# 03_HDMI_TX.net
KiCad netlist of a schematic drawn in Altium Designer
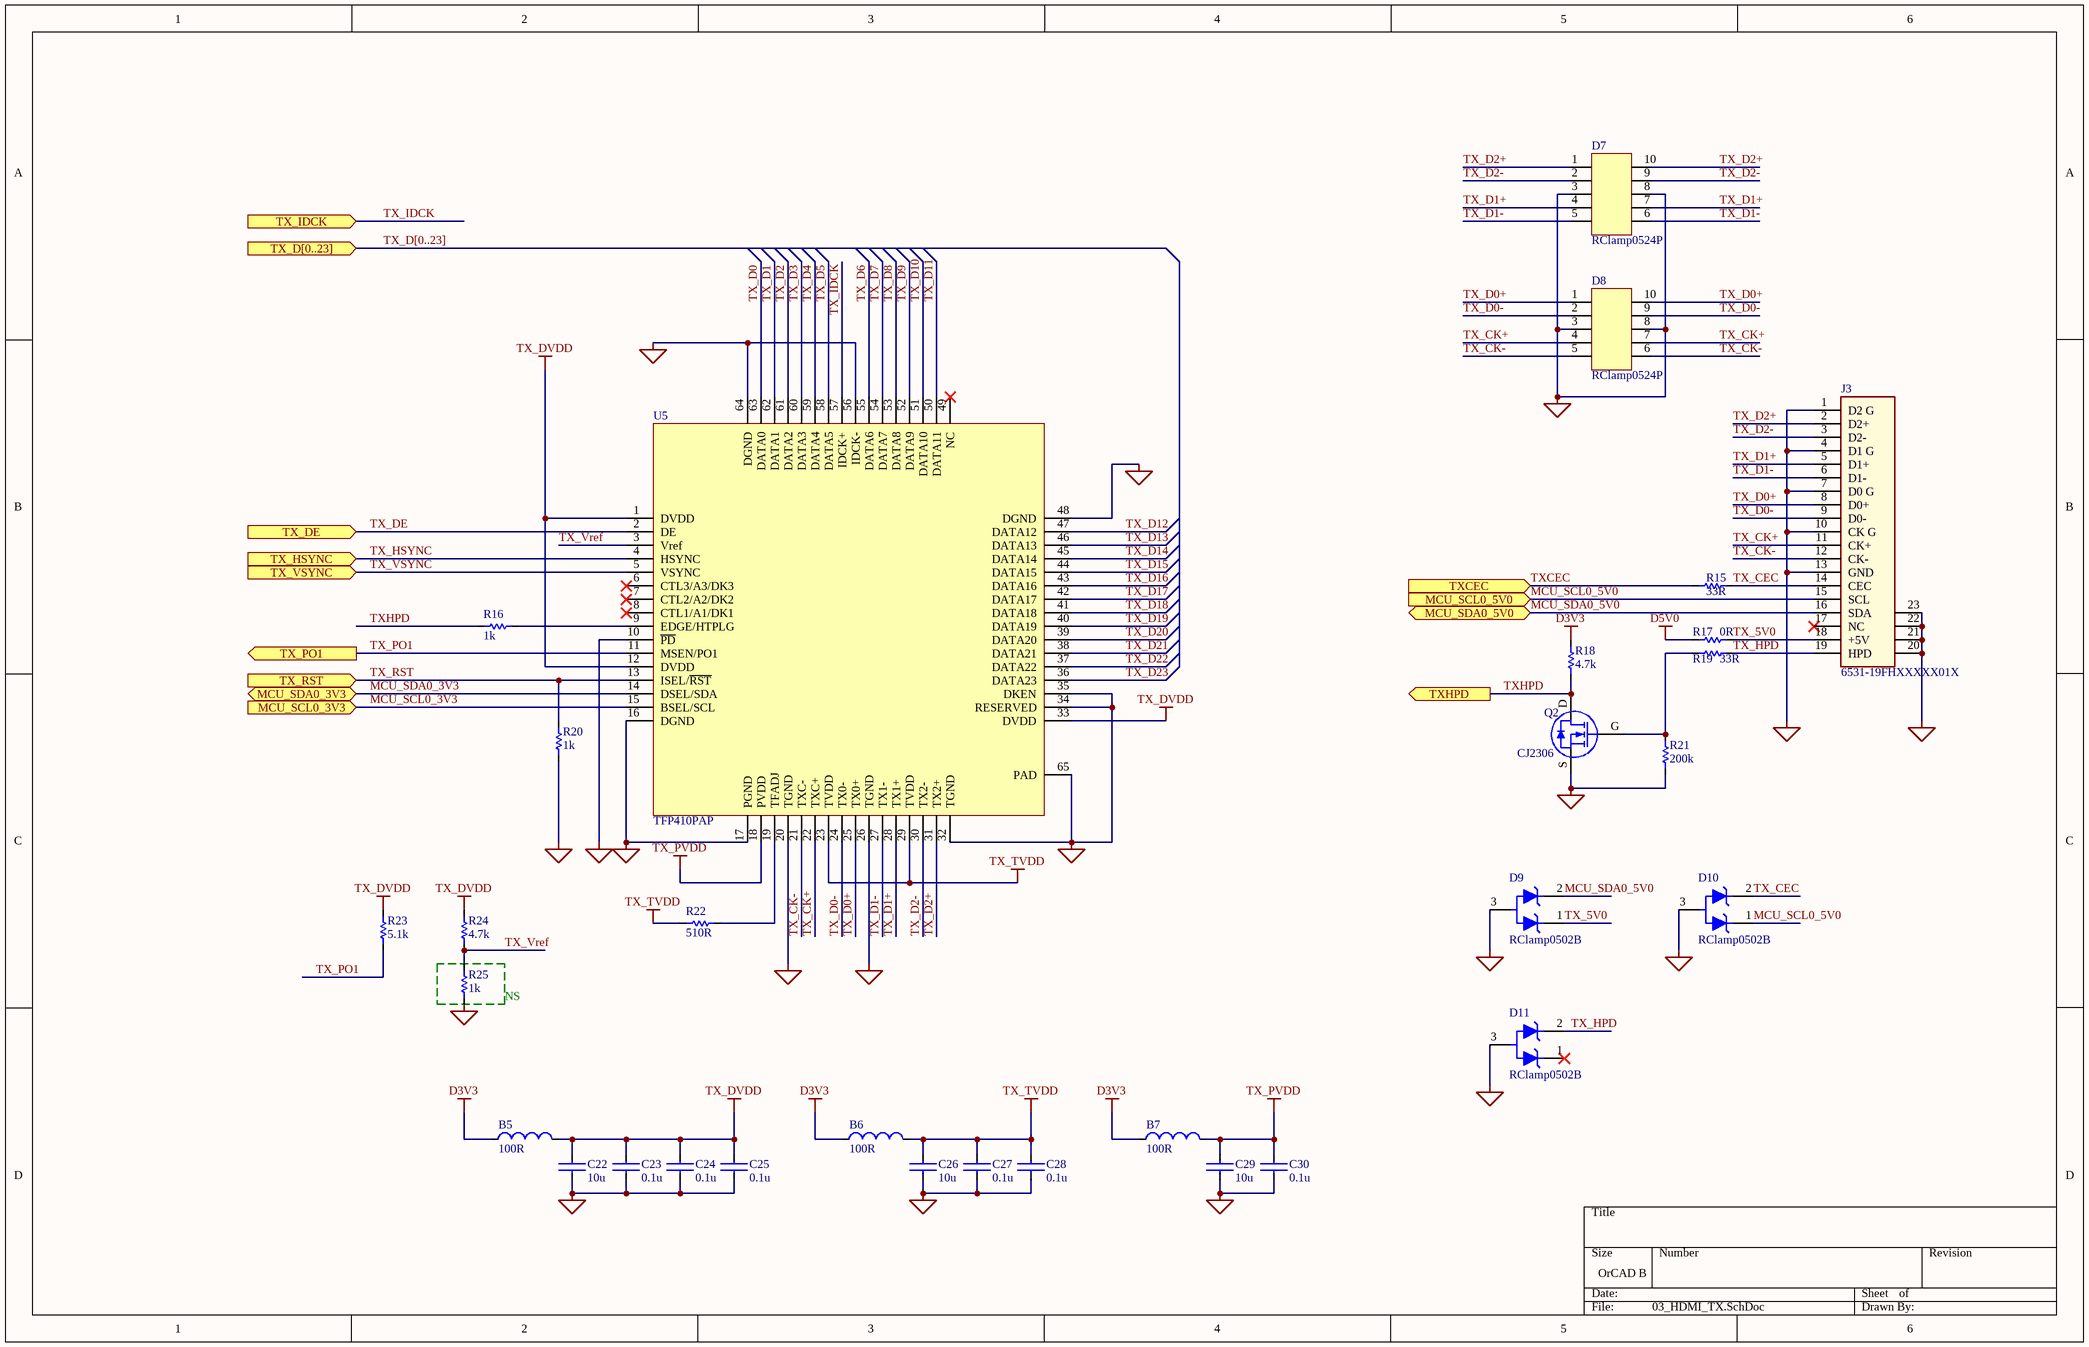
[diagram p0: 03_HDMI_TX.SchDoc]

(export (version "E")
  (design (tool "Eeschema 10.0.6"))
  (components
    (comp (ref "B5")
      (value "100R")
      (footprint "INDC1608X09N_B0603_TAIYO")
      (description "Bead,100R,2500mA,0.035ohm,0603")
      (libsource (lib "AD15_libpkg") (part "FBMH1608HM101-T"))
    )
    (comp (ref "B6")
      (value "100R")
      (footprint "INDC1608X09N_B0603_TAIYO")
      (description "Bead,100R,2500mA,0.035ohm,0603")
      (libsource (lib "AD15_libpkg") (part "FBMH1608HM101-T"))
    )
    (comp (ref "B7")
      (value "100R")
      (footprint "INDC1608X09N_B0603_TAIYO")
      (description "Bead,100R,2500mA,0.035ohm,0603")
      (libsource (lib "AD15_libpkg") (part "FBMH1608HM101-T"))
    )
    (comp (ref "C22")
      (value "10u")
      (footprint "CAPC1608X09N_C0603")
      (description "CAP,Ceramic,X7R,10%,6.3V,10uF,0603")
      (libsource (lib "C0603") (part "CAP113"))
    )
    (comp (ref "C23")
      (value "0.1u")
      (footprint "C0402")
      (description "CAP,Ceramic,X7R,10%,16V,0.1uF,0402")
      (libsource (lib "C0402") (part "CAP011"))
    )
    (comp (ref "C24")
      (value "0.1u")
      (footprint "C0402")
      (description "CAP,Ceramic,X7R,10%,16V,0.1uF,0402")
      (libsource (lib "C0402") (part "CAP011"))
    )
    (comp (ref "C25")
      (value "0.1u")
      (footprint "C0402")
      (description "CAP,Ceramic,X7R,10%,16V,0.1uF,0402")
      (libsource (lib "C0402") (part "CAP011"))
    )
    (comp (ref "C26")
      (value "10u")
      (footprint "CAPC1608X09N_C0603")
      (description "CAP,Ceramic,X7R,10%,6.3V,10uF,0603")
      (libsource (lib "C0603") (part "CAP113"))
    )
    (comp (ref "C27")
      (value "0.1u")
      (footprint "C0402")
      (description "CAP,Ceramic,X7R,10%,16V,0.1uF,0402")
      (libsource (lib "C0402") (part "CAP011"))
    )
    (comp (ref "C28")
      (value "0.1u")
      (footprint "C0402")
      (description "CAP,Ceramic,X7R,10%,16V,0.1uF,0402")
      (libsource (lib "C0402") (part "CAP011"))
    )
    (comp (ref "C29")
      (value "10u")
      (footprint "CAPC1608X09N_C0603")
      (description "CAP,Ceramic,X7R,10%,6.3V,10uF,0603")
      (libsource (lib "C0603") (part "CAP113"))
    )
    (comp (ref "C30")
      (value "0.1u")
      (footprint "C0402")
      (description "CAP,Ceramic,X7R,10%,16V,0.1uF,0402")
      (libsource (lib "C0402") (part "CAP011"))
    )
    (comp (ref "D7")
      (value "RClamp0524P")
      (footprint "SLP2510P8_RClamp0524P")
      (description "TVS array,0.3pF,5V,SLP2510P8")
      (libsource (lib "AD15_libpkg") (part "RClamp0524P"))
    )
    (comp (ref "D8")
      (value "RClamp0524P")
      (footprint "SLP2510P8_RClamp0524P")
      (description "TVS array,0.3pF,5V,SLP2510P8")
      (libsource (lib "AD15_libpkg") (part "RClamp0524P"))
    )
    (comp (ref "D9")
      (value "RClamp0502B")
      (footprint "SOTFL50P160X90-3N_RClamp0502B")
      (description "TVS array,1pF,5V,SC75")
      (libsource (lib "AD15_libpkg") (part "RClamp0502B"))
    )
    (comp (ref "D10")
      (value "RClamp0502B")
      (footprint "SOTFL50P160X90-3N_RClamp0502B")
      (description "TVS array,1pF,5V,SC75")
      (libsource (lib "AD15_libpkg") (part "RClamp0502B"))
    )
    (comp (ref "D11")
      (value "RClamp0502B")
      (footprint "SOTFL50P160X90-3N_RClamp0502B")
      (description "TVS array,1pF,5V,SC75")
      (libsource (lib "AD15_libpkg") (part "RClamp0502B"))
    )
    (comp (ref "J3")
      (value "6531-19FHXXXXX01X")
      (footprint "6531-19FHXXXXX01X")
      (description "Header,HDMI type C,19-Pin,Right angle,0.4mm Pitch,SMD")
      (libsource (lib "AD15_schlib") (part "6531-19FHXXXXX01X"))
    )
    (comp (ref "Q2")
      (value "CJ2306")
      (footprint "SOT95P240X115-3N_JCET_MOSFET")
      (description "MOSFET,N Channel,3.16A,30V,SOT23")
      (libsource (lib "AD15_libpkg") (part "CJ2306"))
    )
    (comp (ref "R15")
      (value "33R")
      (footprint "R0402")
      (description "RES,33R,1%,1/16W,0402")
      (libsource (lib "R0402") (part "RES017"))
    )
    (comp (ref "R16")
      (value "1k")
      (footprint "R0402")
      (description "RES,1k,1%,1/16W,0402")
      (libsource (lib "R0402") (part "RES011"))
    )
    (comp (ref "R17")
      (value "0R")
      (footprint "R0402")
      (description "RES,0R,1%,1/16W,0402")
      (libsource (lib "R0402") (part "RES016"))
    )
    (comp (ref "R18")
      (value "4.7k")
      (footprint "R0402")
      (description "RES,4.7k,1%,1/16W,0402")
      (libsource (lib "R0402") (part "RES015"))
    )
    (comp (ref "R19")
      (value "33R")
      (footprint "R0402")
      (description "RES,33R,1%,1/16W,0402")
      (libsource (lib "R0402") (part "RES017"))
    )
    (comp (ref "R20")
      (value "1k")
      (footprint "R0402")
      (description "RES,1k,1%,1/16W,0402")
      (libsource (lib "R0402") (part "RES011"))
    )
    (comp (ref "R21")
      (value "200k")
      (footprint "R0402")
      (description "RES,200k,1%,1/16W,0402")
      (libsource (lib "R0402") (part "RES0117"))
    )
    (comp (ref "R22")
      (value "510R")
      (footprint "R0402")
      (description "RES,510R,1%,1/16W,0402")
      (libsource (lib "R0402") (part "RES0128"))
    )
    (comp (ref "R23")
      (value "5.1k")
      (footprint "R0402")
      (description "RES,5.1k,1%,1/16W,0402")
      (libsource (lib "R0402") (part "RES014"))
    )
    (comp (ref "R24")
      (value "4.7k")
      (footprint "R0402")
      (description "RES,4.7k,1%,1/16W,0402")
      (libsource (lib "R0402") (part "RES015"))
    )
    (comp (ref "R25")
      (value "1k")
      (footprint "R0402")
      (description "RES,1k,1%,1/16W,0402")
      (libsource (lib "R0402") (part "RES011"))
    )
    (comp (ref "U5")
      (value "TFP410PAP")
      (footprint "TSQFP50P1200X1200X120_HS-65N_TFP410")
      (description "IC,PanelBus Digital Transmitter,HTQFP64")
      (libsource (lib "AD15_libpkg") (part "TFP410"))
    )
  )
  (nets
    (net (code "1") (name "/MCU_SCL0_3V3") (class "Default")
      (node (ref "U5") (pin "15") (pinfunction "BSEL/SCL_15") (pintype "passive"))
    )
    (net (code "2") (name "/MCU_SCL0_5V0") (class "Default")
      (node (ref "D10") (pin "1") (pinfunction "0_1") (pintype "passive"))
      (node (ref "J3") (pin "15") (pinfunction "SCL_15") (pintype "passive"))
    )
    (net (code "3") (name "/MCU_SDA0_3V3") (class "Default")
      (node (ref "U5") (pin "14") (pinfunction "DSEL/SDA_14") (pintype "passive"))
    )
    (net (code "4") (name "/MCU_SDA0_5V0") (class "Default")
      (node (ref "D9") (pin "2") (pinfunction "1_2") (pintype "passive"))
      (node (ref "J3") (pin "16") (pinfunction "SDA_16") (pintype "passive"))
    )
    (net (code "5") (name "/TXCEC") (class "Default")
      (node (ref "R15") (pin "1") (pinfunction "0_1") (pintype "passive"))
    )
    (net (code "6") (name "/TXHPD") (class "Default")
      (node (ref "Q2") (pin "D") (pinfunction "D_D") (pintype "passive"))
      (node (ref "R16") (pin "1") (pinfunction "0_1") (pintype "passive"))
      (node (ref "R18") (pin "1") (pinfunction "0_1") (pintype "passive"))
    )
    (net (code "7") (name "/TX_5V0") (class "Default")
      (node (ref "D9") (pin "1") (pinfunction "0_1") (pintype "passive"))
      (node (ref "J3") (pin "18") (pinfunction "+5V_18") (pintype "passive"))
      (node (ref "R17") (pin "2") (pinfunction "2_2") (pintype "passive"))
    )
    (net (code "8") (name "/TX_CEC") (class "Default")
      (node (ref "D10") (pin "2") (pinfunction "1_2") (pintype "passive"))
      (node (ref "J3") (pin "14") (pinfunction "CEC_14") (pintype "passive"))
      (node (ref "R15") (pin "2") (pinfunction "2_2") (pintype "passive"))
    )
    (net (code "9") (name "/TX_CK+") (class "Default")
      (node (ref "D8") (pin "4") (pinfunction "3_4") (pintype "passive"))
      (node (ref "D8") (pin "7") (pinfunction "6_7") (pintype "passive"))
      (node (ref "J3") (pin "11") (pinfunction "CK+_11") (pintype "passive"))
      (node (ref "U5") (pin "22") (pinfunction "TXC+_22") (pintype "passive"))
    )
    (net (code "10") (name "/TX_CK-") (class "Default")
      (node (ref "D8") (pin "5") (pinfunction "4_5") (pintype "passive"))
      (node (ref "D8") (pin "6") (pinfunction "5_6") (pintype "passive"))
      (node (ref "J3") (pin "12") (pinfunction "CK-_12") (pintype "passive"))
      (node (ref "U5") (pin "21") (pinfunction "TXC-_21") (pintype "passive"))
    )
    (net (code "11") (name "/TX_D0") (class "Default")
      (node (ref "U5") (pin "63") (pinfunction "DATA0_63") (pintype "passive"))
    )
    (net (code "12") (name "/TX_D0+") (class "Default")
      (node (ref "D8") (pin "1") (pinfunction "0_1") (pintype "passive"))
      (node (ref "D8") (pin "10") (pinfunction "9_10") (pintype "passive"))
      (node (ref "J3") (pin "8") (pinfunction "D0+_8") (pintype "passive"))
      (node (ref "U5") (pin "25") (pinfunction "TX0+_25") (pintype "passive"))
    )
    (net (code "13") (name "/TX_D0-") (class "Default")
      (node (ref "D8") (pin "2") (pinfunction "1_2") (pintype "passive"))
      (node (ref "D8") (pin "9") (pinfunction "8_9") (pintype "passive"))
      (node (ref "J3") (pin "9") (pinfunction "D0-_9") (pintype "passive"))
      (node (ref "U5") (pin "24") (pinfunction "TX0-_24") (pintype "passive"))
    )
    (net (code "14") (name "/TX_D1") (class "Default")
      (node (ref "U5") (pin "62") (pinfunction "DATA1_62") (pintype "passive"))
    )
    (net (code "15") (name "/TX_D1+") (class "Default")
      (node (ref "D7") (pin "4") (pinfunction "3_4") (pintype "passive"))
      (node (ref "D7") (pin "7") (pinfunction "6_7") (pintype "passive"))
      (node (ref "J3") (pin "5") (pinfunction "D1+_5") (pintype "passive"))
      (node (ref "U5") (pin "28") (pinfunction "TX1+_28") (pintype "passive"))
    )
    (net (code "16") (name "/TX_D1-") (class "Default")
      (node (ref "D7") (pin "5") (pinfunction "4_5") (pintype "passive"))
      (node (ref "D7") (pin "6") (pinfunction "5_6") (pintype "passive"))
      (node (ref "J3") (pin "6") (pinfunction "D1-_6") (pintype "passive"))
      (node (ref "U5") (pin "27") (pinfunction "TX1-_27") (pintype "passive"))
    )
    (net (code "17") (name "/TX_D2") (class "Default")
      (node (ref "U5") (pin "61") (pinfunction "DATA2_61") (pintype "passive"))
    )
    (net (code "18") (name "/TX_D2+") (class "Default")
      (node (ref "D7") (pin "1") (pinfunction "0_1") (pintype "passive"))
      (node (ref "D7") (pin "10") (pinfunction "9_10") (pintype "passive"))
      (node (ref "J3") (pin "2") (pinfunction "D2+_2") (pintype "passive"))
      (node (ref "U5") (pin "31") (pinfunction "TX2+_31") (pintype "passive"))
    )
    (net (code "19") (name "/TX_D2-") (class "Default")
      (node (ref "D7") (pin "2") (pinfunction "1_2") (pintype "passive"))
      (node (ref "D7") (pin "9") (pinfunction "8_9") (pintype "passive"))
      (node (ref "J3") (pin "3") (pinfunction "D2-_3") (pintype "passive"))
      (node (ref "U5") (pin "30") (pinfunction "TX2-_30") (pintype "passive"))
    )
    (net (code "20") (name "/TX_D3") (class "Default")
      (node (ref "U5") (pin "60") (pinfunction "DATA3_60") (pintype "passive"))
    )
    (net (code "21") (name "/TX_D4") (class "Default")
      (node (ref "U5") (pin "59") (pinfunction "DATA4_59") (pintype "passive"))
    )
    (net (code "22") (name "/TX_D5") (class "Default")
      (node (ref "U5") (pin "58") (pinfunction "DATA5_58") (pintype "passive"))
    )
    (net (code "23") (name "/TX_D6") (class "Default")
      (node (ref "U5") (pin "55") (pinfunction "DATA6_55") (pintype "passive"))
    )
    (net (code "24") (name "/TX_D7") (class "Default")
      (node (ref "U5") (pin "54") (pinfunction "DATA7_54") (pintype "passive"))
    )
    (net (code "25") (name "/TX_D8") (class "Default")
      (node (ref "U5") (pin "53") (pinfunction "DATA8_53") (pintype "passive"))
    )
    (net (code "26") (name "/TX_D9") (class "Default")
      (node (ref "U5") (pin "52") (pinfunction "DATA9_52") (pintype "passive"))
    )
    (net (code "27") (name "/TX_D10") (class "Default")
      (node (ref "U5") (pin "51") (pinfunction "DATA10_51") (pintype "passive"))
    )
    (net (code "28") (name "/TX_D11") (class "Default")
      (node (ref "U5") (pin "50") (pinfunction "DATA11_50") (pintype "passive"))
    )
    (net (code "29") (name "/TX_D12") (class "Default")
      (node (ref "U5") (pin "47") (pinfunction "DATA12_47") (pintype "passive"))
    )
    (net (code "30") (name "/TX_D13") (class "Default")
      (node (ref "U5") (pin "46") (pinfunction "DATA13_46") (pintype "passive"))
    )
    (net (code "31") (name "/TX_D14") (class "Default")
      (node (ref "U5") (pin "45") (pinfunction "DATA14_45") (pintype "passive"))
    )
    (net (code "32") (name "/TX_D15") (class "Default")
      (node (ref "U5") (pin "44") (pinfunction "DATA15_44") (pintype "passive"))
    )
    (net (code "33") (name "/TX_D16") (class "Default")
      (node (ref "U5") (pin "43") (pinfunction "DATA16_43") (pintype "passive"))
    )
    (net (code "34") (name "/TX_D17") (class "Default")
      (node (ref "U5") (pin "42") (pinfunction "DATA17_42") (pintype "passive"))
    )
    (net (code "35") (name "/TX_D18") (class "Default")
      (node (ref "U5") (pin "41") (pinfunction "DATA18_41") (pintype "passive"))
    )
    (net (code "36") (name "/TX_D19") (class "Default")
      (node (ref "U5") (pin "40") (pinfunction "DATA19_40") (pintype "passive"))
    )
    (net (code "37") (name "/TX_D20") (class "Default")
      (node (ref "U5") (pin "39") (pinfunction "DATA20_39") (pintype "passive"))
    )
    (net (code "38") (name "/TX_D21") (class "Default")
      (node (ref "U5") (pin "38") (pinfunction "DATA21_38") (pintype "passive"))
    )
    (net (code "39") (name "/TX_D22") (class "Default")
      (node (ref "U5") (pin "37") (pinfunction "DATA22_37") (pintype "passive"))
    )
    (net (code "40") (name "/TX_D23") (class "Default")
      (node (ref "U5") (pin "36") (pinfunction "DATA23_36") (pintype "passive"))
    )
    (net (code "41") (name "/TX_DE") (class "Default")
      (node (ref "U5") (pin "2") (pinfunction "DE_2") (pintype "passive"))
    )
    (net (code "43") (name "/TX_HPD") (class "Default")
      (node (ref "D11") (pin "2") (pinfunction "1_2") (pintype "passive"))
      (node (ref "J3") (pin "19") (pinfunction "HPD_19") (pintype "passive"))
      (node (ref "R19") (pin "2") (pinfunction "2_2") (pintype "passive"))
    )
    (net (code "44") (name "/TX_HSYNC") (class "Default")
      (node (ref "U5") (pin "4") (pinfunction "HSYNC_4") (pintype "passive"))
    )
    (net (code "45") (name "/TX_IDCK") (class "Default")
      (node (ref "U5") (pin "57") (pinfunction "IDCK+_57") (pintype "passive"))
    )
    (net (code "46") (name "/TX_PO1") (class "Default")
      (node (ref "R23") (pin "1") (pinfunction "0_1") (pintype "passive"))
      (node (ref "U5") (pin "11") (pinfunction "MSEN/PO1_11") (pintype "passive"))
    )
    (net (code "47") (name "/TX_RST") (class "Default")
      (node (ref "R20") (pin "2") (pinfunction "2_2") (pintype "passive"))
      (node (ref "U5") (pin "13") (pinfunction "ISEL/~{RST}_13") (pintype "passive"))
    )
    (net (code "48") (name "/TX_VSYNC") (class "Default")
      (node (ref "U5") (pin "5") (pinfunction "VSYNC_5") (pintype "passive"))
    )
    (net (code "49") (name "/TX_Vref") (class "Default")
      (node (ref "R24") (pin "1") (pinfunction "0_1") (pintype "passive"))
      (node (ref "R25") (pin "2") (pinfunction "2_2") (pintype "passive"))
      (node (ref "U5") (pin "3") (pinfunction "Vref_3") (pintype "passive"))
    )
    (net (code "50") (name "D3V3") (class "Default")
      (node (ref "B5") (pin "2") (pinfunction "1_2") (pintype "passive"))
      (node (ref "B6") (pin "2") (pinfunction "1_2") (pintype "passive"))
      (node (ref "B7") (pin "2") (pinfunction "1_2") (pintype "passive"))
      (node (ref "R18") (pin "2") (pinfunction "2_2") (pintype "passive"))
    )
    (net (code "51") (name "D5V0") (class "Default")
      (node (ref "R17") (pin "1") (pinfunction "0_1") (pintype "passive"))
    )
    (net (code "52") (name "GND") (class "Default")
      (node (ref "C22") (pin "2") (pinfunction "1_2") (pintype "passive"))
      (node (ref "C23") (pin "2") (pinfunction "1_2") (pintype "passive"))
      (node (ref "C24") (pin "2") (pinfunction "1_2") (pintype "passive"))
      (node (ref "C25") (pin "2") (pinfunction "1_2") (pintype "passive"))
      (node (ref "C26") (pin "2") (pinfunction "1_2") (pintype "passive"))
      (node (ref "C27") (pin "2") (pinfunction "1_2") (pintype "passive"))
      (node (ref "C28") (pin "2") (pinfunction "1_2") (pintype "passive"))
      (node (ref "C29") (pin "2") (pinfunction "1_2") (pintype "passive"))
      (node (ref "C30") (pin "2") (pinfunction "1_2") (pintype "passive"))
      (node (ref "D10") (pin "3") (pinfunction "2_3") (pintype "passive"))
      (node (ref "D11") (pin "3") (pinfunction "2_3") (pintype "passive"))
      (node (ref "D7") (pin "3") (pinfunction "2_3") (pintype "passive"))
      (node (ref "D7") (pin "8") (pinfunction "7_8") (pintype "passive"))
      (node (ref "D8") (pin "3") (pinfunction "2_3") (pintype "passive"))
      (node (ref "D8") (pin "8") (pinfunction "7_8") (pintype "passive"))
      (node (ref "D9") (pin "3") (pinfunction "2_3") (pintype "passive"))
      (node (ref "J3") (pin "1") (pinfunction "D2_G_1") (pintype "passive"))
      (node (ref "J3") (pin "10") (pinfunction "CK_G_10") (pintype "passive"))
      (node (ref "J3") (pin "13") (pinfunction "GND_13") (pintype "passive"))
      (node (ref "J3") (pin "20") (pinfunction "3_20") (pintype "passive"))
      (node (ref "J3") (pin "21") (pinfunction "4_21") (pintype "passive"))
      (node (ref "J3") (pin "22") (pinfunction "5_22") (pintype "passive"))
      (node (ref "J3") (pin "23") (pinfunction "6_23") (pintype "passive"))
      (node (ref "J3") (pin "4") (pinfunction "D1_G_4") (pintype "passive"))
      (node (ref "J3") (pin "7") (pinfunction "D0_G_7") (pintype "passive"))
      (node (ref "Q2") (pin "S") (pinfunction "S_S") (pintype "passive"))
      (node (ref "R20") (pin "1") (pinfunction "0_1") (pintype "passive"))
      (node (ref "R21") (pin "1") (pinfunction "0_1") (pintype "passive"))
      (node (ref "R25") (pin "1") (pinfunction "0_1") (pintype "passive"))
      (node (ref "U5") (pin "10") (pinfunction "~{PD}_10") (pintype "passive"))
      (node (ref "U5") (pin "16") (pinfunction "DGND_16") (pintype "passive"))
      (node (ref "U5") (pin "17") (pinfunction "PGND_17") (pintype "passive"))
      (node (ref "U5") (pin "20") (pinfunction "TGND_20") (pintype "passive"))
      (node (ref "U5") (pin "26") (pinfunction "TGND_26") (pintype "passive"))
      (node (ref "U5") (pin "32") (pinfunction "TGND_32") (pintype "passive"))
      (node (ref "U5") (pin "34") (pinfunction "RESERVED_34") (pintype "passive"))
      (node (ref "U5") (pin "35") (pinfunction "DKEN_35") (pintype "passive"))
      (node (ref "U5") (pin "48") (pinfunction "DGND_48") (pintype "passive"))
      (node (ref "U5") (pin "56") (pinfunction "IDCK-_56") (pintype "passive"))
      (node (ref "U5") (pin "64") (pinfunction "DGND_64") (pintype "passive"))
      (node (ref "U5") (pin "65") (pinfunction "PAD_65") (pintype "passive"))
    )
    (net (code "53") (name "Net-(R19-0)") (class "Default")
      (node (ref "Q2") (pin "G") (pinfunction "G_G") (pintype "passive"))
      (node (ref "R19") (pin "1") (pinfunction "0_1") (pintype "passive"))
      (node (ref "R21") (pin "2") (pinfunction "2_2") (pintype "passive"))
    )
    (net (code "54") (name "Net-(U5-EDGE{slash}HTPLG)") (class "Default")
      (node (ref "R16") (pin "2") (pinfunction "2_2") (pintype "passive"))
      (node (ref "U5") (pin "9") (pinfunction "EDGE/HTPLG_9") (pintype "passive"))
    )
    (net (code "55") (name "Net-(U5-TFADJ)") (class "Default")
      (node (ref "R22") (pin "2") (pinfunction "2_2") (pintype "passive"))
      (node (ref "U5") (pin "19") (pinfunction "TFADJ_19") (pintype "passive"))
    )
    (net (code "56") (name "TX_DVDD") (class "Default")
      (node (ref "B5") (pin "1") (pinfunction "0_1") (pintype "passive"))
      (node (ref "C22") (pin "1") (pinfunction "0_1") (pintype "passive"))
      (node (ref "C23") (pin "1") (pinfunction "0_1") (pintype "passive"))
      (node (ref "C24") (pin "1") (pinfunction "0_1") (pintype "passive"))
      (node (ref "C25") (pin "1") (pinfunction "0_1") (pintype "passive"))
      (node (ref "R23") (pin "2") (pinfunction "2_2") (pintype "passive"))
      (node (ref "R24") (pin "2") (pinfunction "2_2") (pintype "passive"))
      (node (ref "U5") (pin "1") (pinfunction "DVDD_1") (pintype "passive"))
      (node (ref "U5") (pin "12") (pinfunction "DVDD_12") (pintype "passive"))
      (node (ref "U5") (pin "33") (pinfunction "DVDD_33") (pintype "passive"))
    )
    (net (code "57") (name "TX_PVDD") (class "Default")
      (node (ref "B7") (pin "1") (pinfunction "0_1") (pintype "passive"))
      (node (ref "C29") (pin "1") (pinfunction "0_1") (pintype "passive"))
      (node (ref "C30") (pin "1") (pinfunction "0_1") (pintype "passive"))
      (node (ref "U5") (pin "18") (pinfunction "PVDD_18") (pintype "passive"))
    )
    (net (code "58") (name "TX_TVDD") (class "Default")
      (node (ref "B6") (pin "1") (pinfunction "0_1") (pintype "passive"))
      (node (ref "C26") (pin "1") (pinfunction "0_1") (pintype "passive"))
      (node (ref "C27") (pin "1") (pinfunction "0_1") (pintype "passive"))
      (node (ref "C28") (pin "1") (pinfunction "0_1") (pintype "passive"))
      (node (ref "R22") (pin "1") (pinfunction "0_1") (pintype "passive"))
      (node (ref "U5") (pin "23") (pinfunction "TVDD_23") (pintype "passive"))
      (node (ref "U5") (pin "29") (pinfunction "TVDD_29") (pintype "passive"))
    )
    (net (code "59") (name "unconnected-(D11-0-Pad1)") (class "Default")
      (node (ref "D11") (pin "1") (pinfunction "0_1") (pintype "passive+no_connect"))
    )
    (net (code "60") (name "unconnected-(J3-NC-Pad17)") (class "Default")
      (node (ref "J3") (pin "17") (pinfunction "NC_17") (pintype "passive+no_connect"))
    )
    (net (code "61") (name "unconnected-(U5-CTL1{slash}A1{slash}DK1-Pad8)") (class "Default")
      (node (ref "U5") (pin "8") (pinfunction "CTL1/A1/DK1_8") (pintype "passive+no_connect"))
    )
    (net (code "62") (name "unconnected-(U5-CTL2{slash}A2{slash}DK2-Pad7)") (class "Default")
      (node (ref "U5") (pin "7") (pinfunction "CTL2/A2/DK2_7") (pintype "passive+no_connect"))
    )
    (net (code "63") (name "unconnected-(U5-CTL3{slash}A3{slash}DK3-Pad6)") (class "Default")
      (node (ref "U5") (pin "6") (pinfunction "CTL3/A3/DK3_6") (pintype "passive+no_connect"))
    )
    (net (code "64") (name "unconnected-(U5-NC-Pad49)") (class "Default")
      (node (ref "U5") (pin "49") (pinfunction "NC_49") (pintype "passive+no_connect"))
    )
  )
)
